# RS485.net
KiCad netlist of a schematic drawn in Altium Designer
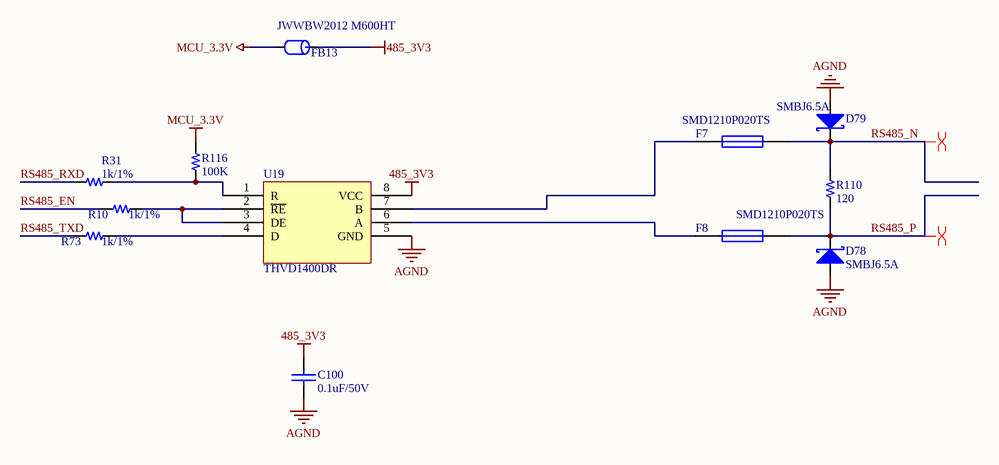
[diagram p0: RS485.SchDoc]

(export (version "E")
  (design (tool "Eeschema 10.0.6"))
  (components
    (comp (ref "C100")
      (value "0.1uF/50V")
      (footprint "CAPC1608X092N_0603")
      (fields (field (name "PARTNUMBER") "CC0603KRX7R9BB104"))
      (libsource (lib "*") (part "CAP"))
    )
    (comp (ref "D78") (value "SMBJ6.5A") (footprint "SMB") (libsource (lib "*") (part "DIODE S")))
    (comp (ref "D79") (value "SMBJ6.5A") (footprint "SMB") (libsource (lib "*") (part "DIODE S")))
    (comp (ref "F7")
      (value "SMD1210P020TS")
      (footprint "RESC3216X070N_1206")
      (fields (field (name "PARTNUMBER") "SMD1210-020") (field (name "PUBLISHER") "Altium Limited"))
      (libsource (lib "Miscellaneous Devices") (part "Fuse 1"))
    )
    (comp (ref "F8")
      (value "SMD1210P020TS")
      (footprint "RESC3216X070N_1206")
      (fields (field (name "PARTNUMBER") "SMD1210-020") (field (name "PUBLISHER") "Altium Limited"))
      (libsource (lib "Miscellaneous Devices") (part "Fuse 1"))
    )
    (comp (ref "FB13")
      (value "JWWBW2012 M600HT")
      (footprint "0805CZ")
      (fields (field (name "PARTNUMBER") "BLM21PG221SN1D"))
      (libsource (lib "Schlib_20110825") (part "FB"))
    )
    (comp (ref "R10")
      (value "1k/1%")
      (footprint "RESC1608X055N_0603")
      (fields (field (name "PARTNUMBER") "RC0603FR-071KL"))
      (libsource (lib "JRJ_1") (part "R"))
    )
    (comp (ref "R31")
      (value "1k/1%")
      (footprint "RESC1608X055N_0603")
      (fields (field (name "PARTNUMBER") "RC0603FR-071KL"))
      (libsource (lib "JRJ_1") (part "R"))
    )
    (comp (ref "R73")
      (value "1k/1%")
      (footprint "RESC1608X055N_0603")
      (fields (field (name "PARTNUMBER") "RC0603FR-071KL"))
      (libsource (lib "JRJ_1") (part "R"))
    )
    (comp (ref "R110")
      (value "120")
      (footprint "RESC1608X055N_0603")
      (fields (field (name "PARTNUMBER") "RC0603FR-07120RL"))
      (libsource (lib "JRJ_1") (part "R"))
    )
    (comp (ref "R116")
      (value "100K")
      (footprint "RESC1608X055N_0603")
      (fields (field (name "PARTNUMBER") "RC0603FR-07100KL"))
      (libsource (lib "JRJ_1") (part "R"))
    )
    (comp (ref "U19")
      (value "THVD1400DR")
      (footprint "so-8")
      (fields (field (name "PARTNUMBER") "BL3085"))
      (libsource (lib "Schlib1") (part "SN65HVD06D"))
    )
  )
  (nets
    (net (code "1") (name "/RS485_EN") (class "Default") (node (ref "R10") (pin "2") (pintype "passive")))
    (net (code "2") (name "/RS485_N") (class "Default")
      (node (ref "D79") (pin "2") (pinfunction "K_2") (pintype "passive"))
      (node (ref "F7") (pin "2") (pinfunction "2_2") (pintype "passive"))
      (node (ref "R110") (pin "1") (pintype "passive"))
    )
    (net (code "3") (name "/RS485_P") (class "Default")
      (node (ref "D78") (pin "2") (pinfunction "K_2") (pintype "passive"))
      (node (ref "F8") (pin "2") (pinfunction "2_2") (pintype "passive"))
      (node (ref "R110") (pin "2") (pintype "passive"))
    )
    (net (code "4") (name "/RS485_RXD") (class "Default") (node (ref "R31") (pin "2") (pintype "passive")))
    (net (code "5") (name "/RS485_TXD") (class "Default") (node (ref "R73") (pin "2") (pintype "passive")))
    (net (code "6") (name "485_3V3") (class "Default")
      (node (ref "C100") (pin "2") (pinfunction "2_2") (pintype "passive"))
      (node (ref "FB13") (pin "1") (pintype "passive"))
      (node (ref "U19") (pin "8") (pinfunction "VCC_8") (pintype "passive"))
    )
    (net (code "7") (name "AGND") (class "Default")
      (node (ref "C100") (pin "1") (pinfunction "1_1") (pintype "passive"))
      (node (ref "D78") (pin "1") (pinfunction "A_1") (pintype "passive"))
      (node (ref "D79") (pin "1") (pinfunction "A_1") (pintype "passive"))
      (node (ref "U19") (pin "5") (pinfunction "GND_5") (pintype "passive"))
    )
    (net (code "8") (name "MCU_3.3V") (class "Default")
      (node (ref "FB13") (pin "2") (pintype "passive"))
      (node (ref "R116") (pin "2") (pintype "passive"))
    )
    (net (code "9") (name "Net-(U19-A)") (class "Default")
      (node (ref "F8") (pin "1") (pinfunction "1_1") (pintype "passive"))
      (node (ref "U19") (pin "6") (pinfunction "A_6") (pintype "passive"))
    )
    (net (code "10") (name "Net-(U19-B)") (class "Default")
      (node (ref "F7") (pin "1") (pinfunction "1_1") (pintype "passive"))
      (node (ref "U19") (pin "7") (pinfunction "B_7") (pintype "passive"))
    )
    (net (code "11") (name "Net-(U19-D)") (class "Default")
      (node (ref "R73") (pin "1") (pintype "passive"))
      (node (ref "U19") (pin "4") (pinfunction "D_4") (pintype "passive"))
    )
    (net (code "12") (name "Net-(U19-DE)") (class "Default")
      (node (ref "R10") (pin "1") (pintype "passive"))
      (node (ref "U19") (pin "2") (pinfunction "~{RE}_2") (pintype "passive"))
      (node (ref "U19") (pin "3") (pinfunction "DE_3") (pintype "passive"))
    )
    (net (code "13") (name "Net-(U19-R)") (class "Default")
      (node (ref "R116") (pin "1") (pintype "passive"))
      (node (ref "R31") (pin "1") (pintype "passive"))
      (node (ref "U19") (pin "1") (pinfunction "R_1") (pintype "passive"))
    )
  )
)
